# IMX7S_DEBUG.net
KiCad netlist of a schematic drawn in Altium Designer
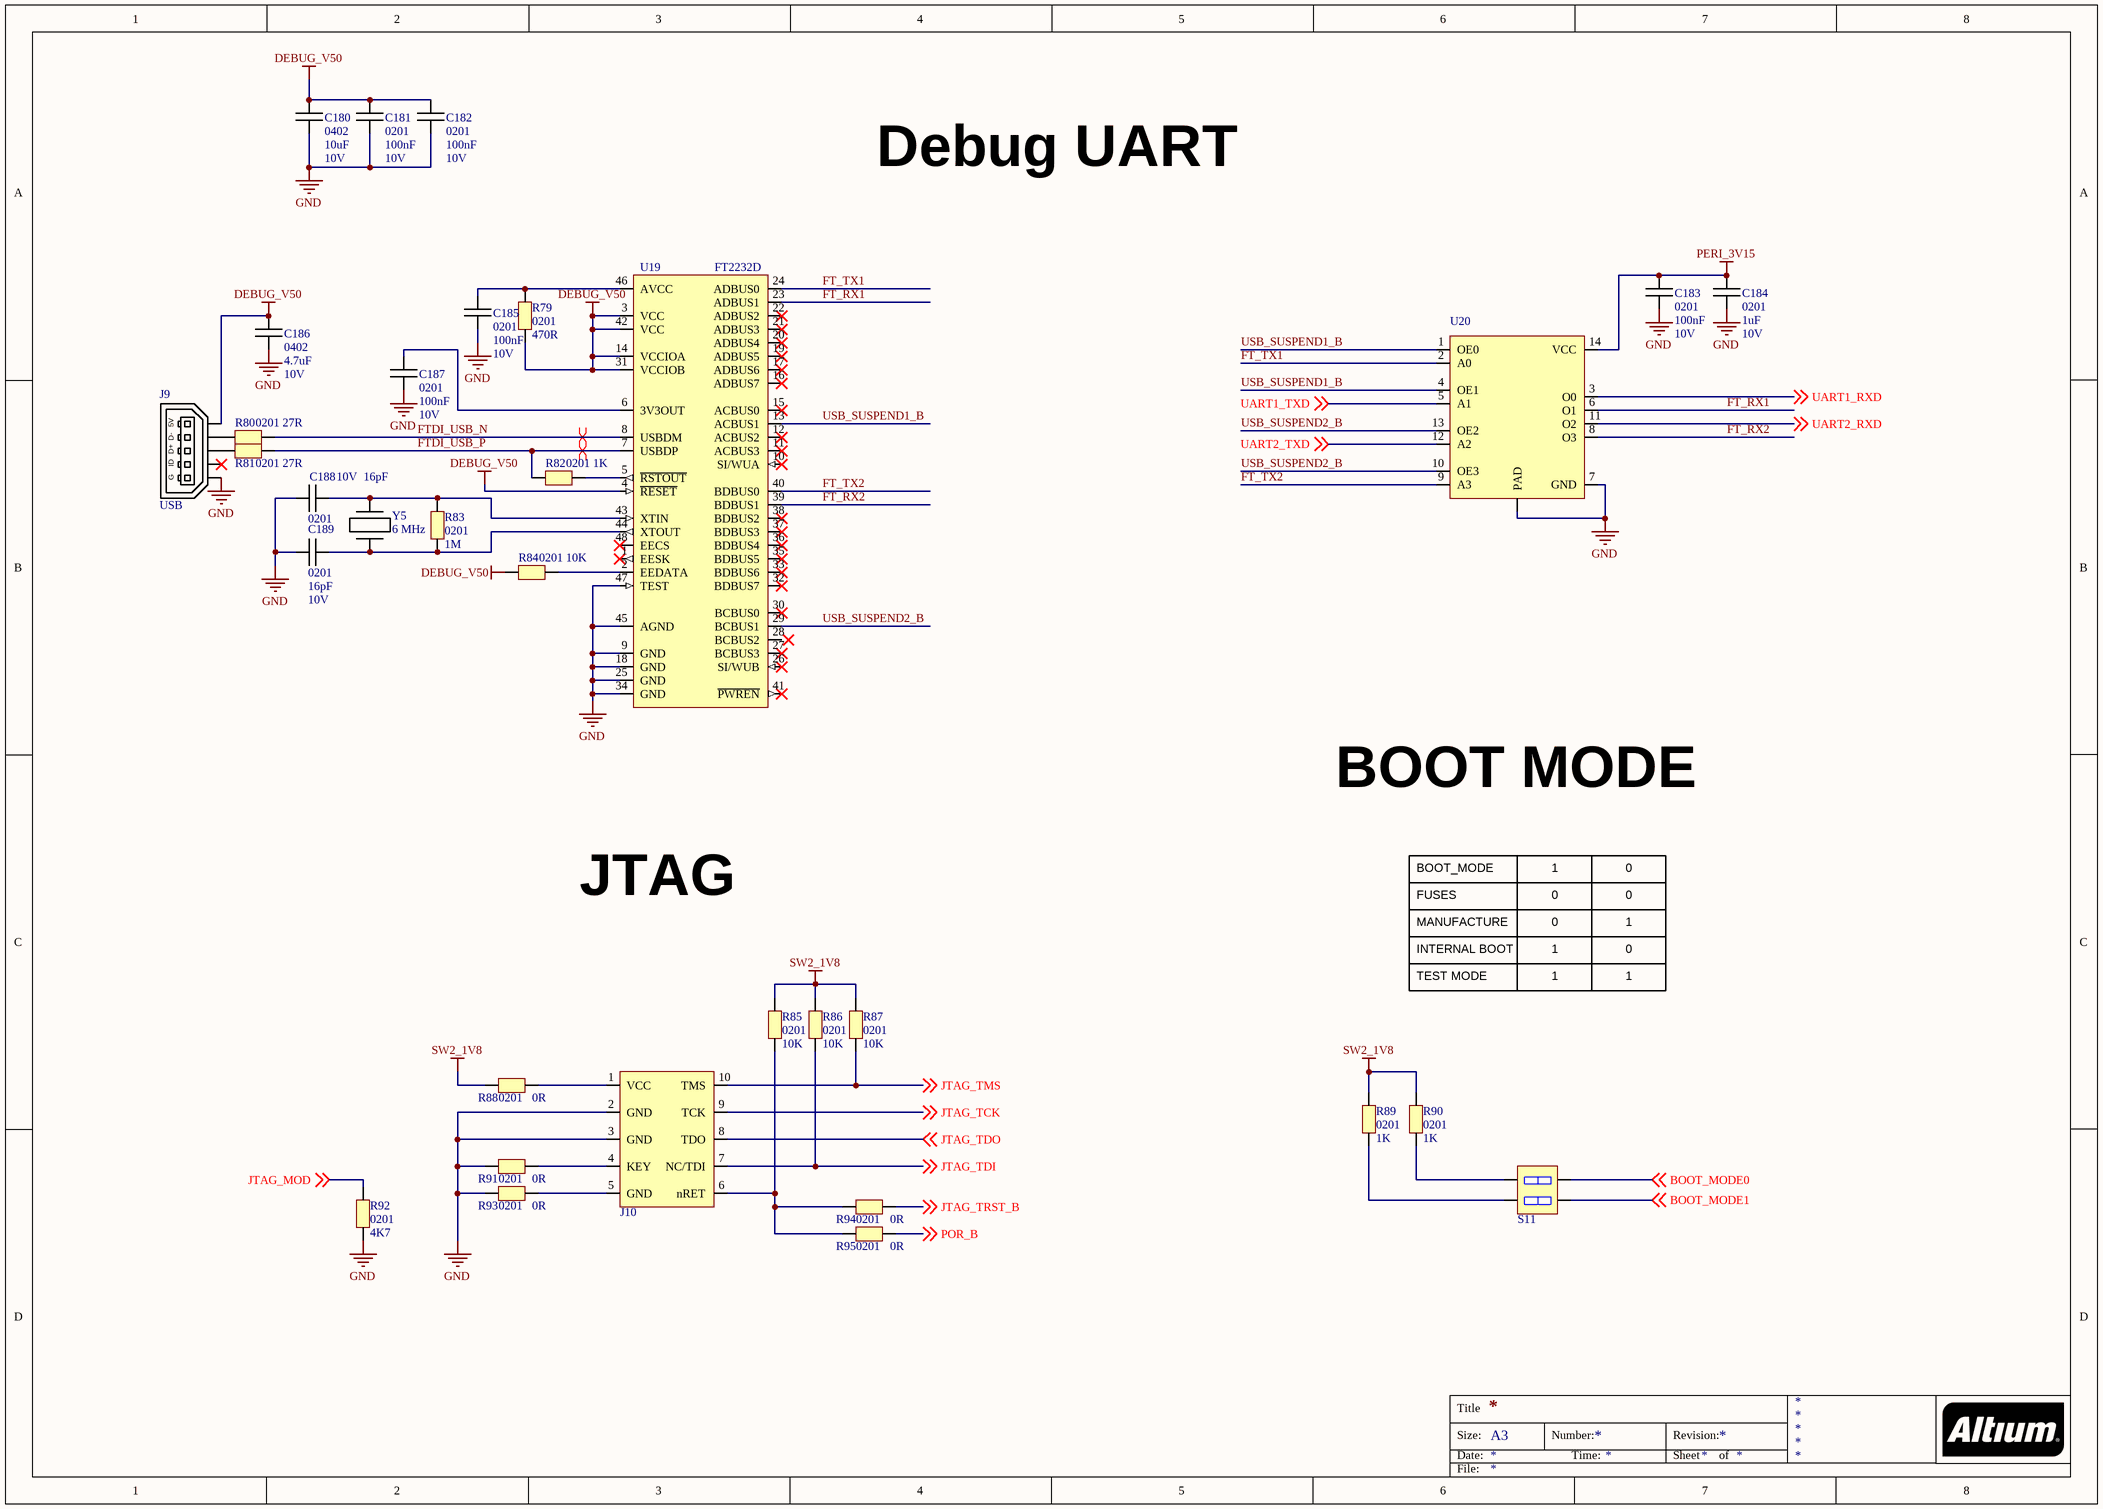
[diagram p0: IMX7S_DEBUG.SchDoc]

(export (version "E")
  (design (tool "Eeschema 10.0.6"))
  (components
    (comp (ref "C180")
      (value "10uF")
      (footprint "C0402")
      (description "Smd Multilayer Ceramic Capacitor, Grm Series, 10 F, 20%, X5r, 6.3 V, 0402 [1005 Metric]")
      (fields
        (field (name "PACKAGE") "0402")
        (field (name "VOLTAGE") "10V")
        (field (name "TOLERANCE") "20%")
        (field (name "Comment") "C0402")
      )
      (libsource (lib "Schlib_IMX7") (part "C0402"))
    )
    (comp (ref "C181")
      (value "100nF")
      (footprint "C0201")
      (description "CAP CER 0.1UF 10V X5R 0201")
      (fields
        (field (name "PACKAGE") "0201")
        (field (name "VOLTAGE") "10V")
        (field (name "TOLERANCE") "10%")
        (field (name "Comment") "C0201")
      )
      (libsource (lib "Schlib_IMX7") (part "C0201"))
    )
    (comp (ref "C182")
      (value "100nF")
      (footprint "C0201")
      (description "CAP CER 0.1UF 10V X5R 0201")
      (fields
        (field (name "PACKAGE") "0201")
        (field (name "VOLTAGE") "10V")
        (field (name "TOLERANCE") "10%")
        (field (name "Comment") "C0201")
      )
      (libsource (lib "Schlib_IMX7") (part "C0201"))
    )
    (comp (ref "C183")
      (value "100nF")
      (footprint "C0201")
      (description "CAP CER 0.1UF 10V X5R 0201")
      (fields
        (field (name "PACKAGE") "0201")
        (field (name "VOLTAGE") "10V")
        (field (name "TOLERANCE") "10%")
        (field (name "Comment") "C0201")
      )
      (libsource (lib "Schlib_IMX7") (part "C0201"))
    )
    (comp (ref "C184")
      (value "1uF")
      (footprint "C0201")
      (description "CAP CER 1UF 6.3V X5R 0201")
      (fields
        (field (name "PACKAGE") "0201")
        (field (name "VOLTAGE") "10V")
        (field (name "TOLERANCE") "20%")
        (field (name "Comment") "C0201")
      )
      (libsource (lib "Schlib_IMX7") (part "C0201"))
    )
    (comp (ref "C185")
      (value "100nF")
      (footprint "C0201")
      (description "CAP CER 0.1UF 10V X5R 0201")
      (fields
        (field (name "PACKAGE") "0201")
        (field (name "VOLTAGE") "10V")
        (field (name "TOLERANCE") "10%")
        (field (name "Comment") "C0201")
      )
      (libsource (lib "Schlib_IMX7") (part "C0201"))
    )
    (comp (ref "C186")
      (value "4.7uF")
      (footprint "C0402")
      (description "0402 10 V 4.7 uF ±20% Tolerance X5R Multilayer Ceramic Chip Capacitor")
      (fields (field (name "PACKAGE") "0402") (field (name "VOLTAGE") "10V") (field (name "Comment") "C0402"))
      (libsource (lib "Schlib_IMX7") (part "C0402"))
    )
    (comp (ref "C187")
      (value "100nF")
      (footprint "C0201")
      (description "CAP CER 0.1UF 10V X5R 0201")
      (fields
        (field (name "PACKAGE") "0201")
        (field (name "VOLTAGE") "10V")
        (field (name "TOLERANCE") "10%")
        (field (name "Comment") "C0201")
      )
      (libsource (lib "Schlib_IMX7") (part "C0201"))
    )
    (comp (ref "C188")
      (value "16pF")
      (footprint "C0201")
      (description "Multilayer Ceramic Capacitors MLCC - SMD/SMT 0201 16pF 50volts C0G +/-5%")
      (fields
        (field (name "PACKAGE") "0201")
        (field (name "VOLTAGE") "10V")
        (field (name "TOLERANCE") "5%")
        (field (name "Comment") "C0201")
      )
      (libsource (lib "Schlib_IMX7") (part "C0201"))
    )
    (comp (ref "C189")
      (value "16pF")
      (footprint "C0201")
      (description "Multilayer Ceramic Capacitors MLCC - SMD/SMT 0201 16pF 50volts C0G +/-5%")
      (fields
        (field (name "PACKAGE") "0201")
        (field (name "VOLTAGE") "10V")
        (field (name "TOLERANCE") "5%")
        (field (name "Comment") "C0201")
      )
      (libsource (lib "Schlib_IMX7") (part "C0201"))
    )
    (comp (ref "J9") (value "USB") (footprint "MICRO_USB") (libsource (lib "Schlib_IMX7") (part "MICRO_USB")))
    (comp (ref "J10")
      (value "CONN_JTAG")
      (footprint "JTAG_CONN")
      (libsource (lib "Schlib_IMX7") (part "CONN_JTAG"))
    )
    (comp (ref "R79")
      (value "470R")
      (footprint "R0201")
      (fields
        (field (name "PACKAGE") "0201")
        (field (name "VOLTAGE") "0V")
        (field (name "TOLERANCE") "1%")
        (field (name "Comment") "R0201")
      )
      (libsource (lib "") (part "R0201_1"))
    )
    (comp (ref "R80")
      (value "27R")
      (footprint "R0201")
      (description "RES SMD 27 OHM 1% 1/20W 0201")
      (fields (field (name "PACKAGE") "0201") (field (name "VOLTAGE") "0V") (field (name "TOLERANCE") "1%"))
      (libsource (lib "Schlib_IMX7") (part "R0201"))
    )
    (comp (ref "R81")
      (value "27R")
      (footprint "R0201")
      (description "RES SMD 27 OHM 1% 1/20W 0201")
      (fields (field (name "PACKAGE") "0201") (field (name "VOLTAGE") "0V") (field (name "TOLERANCE") "1%"))
      (libsource (lib "Schlib_IMX7") (part "R0201"))
    )
    (comp (ref "R82")
      (value "1K")
      (footprint "R0201")
      (fields
        (field (name "PACKAGE") "0201")
        (field (name "VOLTAGE") "0V")
        (field (name "TOLERANCE") "1%")
        (field (name "Comment") "R0201")
      )
      (libsource (lib "Schlib_IMX7") (part "R0201"))
    )
    (comp (ref "R83")
      (value "1M")
      (footprint "R0201")
      (description "RESISTOR, 0201, 1M1, 1%")
      (fields (field (name "PACKAGE") "0201") (field (name "VOLTAGE") "0V") (field (name "TOLERANCE") "1%"))
      (libsource (lib "") (part "R0201_2"))
    )
    (comp (ref "R84")
      (value "10K")
      (footprint "R0201")
      (fields
        (field (name "PACKAGE") "0201")
        (field (name "VOLTAGE") "0V")
        (field (name "TOLERANCE") "1%")
        (field (name "Comment") "R0201")
      )
      (libsource (lib "Schlib_IMX7") (part "R0201"))
    )
    (comp (ref "R85")
      (value "10K")
      (footprint "R0201")
      (fields
        (field (name "PACKAGE") "0201")
        (field (name "VOLTAGE") "0V")
        (field (name "TOLERANCE") "1%")
        (field (name "Comment") "R0201")
      )
      (libsource (lib "") (part "R0201_1"))
    )
    (comp (ref "R86")
      (value "10K")
      (footprint "R0201")
      (fields
        (field (name "PACKAGE") "0201")
        (field (name "VOLTAGE") "0V")
        (field (name "TOLERANCE") "1%")
        (field (name "Comment") "R0201")
      )
      (libsource (lib "") (part "R0201_2"))
    )
    (comp (ref "R87")
      (value "10K")
      (footprint "R0201")
      (fields
        (field (name "PACKAGE") "0201")
        (field (name "VOLTAGE") "0V")
        (field (name "TOLERANCE") "1%")
        (field (name "Comment") "R0201")
      )
      (libsource (lib "") (part "R0201_2"))
    )
    (comp (ref "R88")
      (value "0R")
      (footprint "R0201")
      (description "MULTICOMP - MCRE000086 - RES, 0R0, 1%, 0.05W, 0201, THICK FILM")
      (fields (field (name "PACKAGE") "0201") (field (name "VOLTAGE") "0V") (field (name "TOLERANCE") "1%"))
      (libsource (lib "Schlib_IMX7") (part "R0201"))
    )
    (comp (ref "R89")
      (value "1K")
      (footprint "R0201")
      (fields
        (field (name "PACKAGE") "0201")
        (field (name "VOLTAGE") "0V")
        (field (name "TOLERANCE") "1%")
        (field (name "Comment") "R0201")
      )
      (libsource (lib "") (part "R0201_1"))
    )
    (comp (ref "R90")
      (value "1K")
      (footprint "R0201")
      (fields
        (field (name "PACKAGE") "0201")
        (field (name "VOLTAGE") "0V")
        (field (name "TOLERANCE") "1%")
        (field (name "Comment") "R0201")
      )
      (libsource (lib "") (part "R0201_1"))
    )
    (comp (ref "R91")
      (value "0R")
      (footprint "R0201")
      (description "MULTICOMP - MCRE000086 - RES, 0R0, 1%, 0.05W, 0201, THICK FILM")
      (fields (field (name "PACKAGE") "0201") (field (name "VOLTAGE") "0V") (field (name "TOLERANCE") "1%"))
      (libsource (lib "Schlib_IMX7") (part "R0201"))
    )
    (comp (ref "R92")
      (value "4K7")
      (footprint "R0201")
      (description "RES SMD 4.7K OHM 1% 1/20W 0201")
      (fields (field (name "PACKAGE") "0201") (field (name "VOLTAGE") "0V") (field (name "TOLERANCE") "1%"))
      (libsource (lib "") (part "R0201_2"))
    )
    (comp (ref "R93")
      (value "0R")
      (footprint "R0201")
      (description "MULTICOMP - MCRE000086 - RES, 0R0, 1%, 0.05W, 0201, THICK FILM")
      (fields (field (name "PACKAGE") "0201") (field (name "VOLTAGE") "0V") (field (name "TOLERANCE") "1%"))
      (libsource (lib "Schlib_IMX7") (part "R0201"))
    )
    (comp (ref "R94")
      (value "0R")
      (footprint "R0201")
      (description "MULTICOMP - MCRE000086 - RES, 0R0, 1%, 0.05W, 0201, THICK FILM")
      (fields (field (name "PACKAGE") "0201") (field (name "VOLTAGE") "0V") (field (name "TOLERANCE") "1%"))
      (libsource (lib "Schlib_IMX7") (part "R0201"))
    )
    (comp (ref "R95")
      (value "0R")
      (footprint "R0201")
      (description "MULTICOMP - MCRE000086 - RES, 0R0, 1%, 0.05W, 0201, THICK FILM")
      (fields (field (name "PACKAGE") "0201") (field (name "VOLTAGE") "0V") (field (name "TOLERANCE") "1%"))
      (libsource (lib "Schlib_IMX7") (part "R0201"))
    )
    (comp (ref "S11")
      (value "mikroswitch")
      (footprint "DIP_SWITCH")
      (libsource (lib "Schlib_IMX7") (part "mikroswitch"))
    )
    (comp (ref "U19")
      (value "FT2232D")
      (footprint "LQFP48")
      (description "USB Full Speed to Dual Channel Serial UART/FIFO/JTAG/SPI/I2C IC - LQFP-48")
      (fields (field (name "MF") "FTDI,") (field (name "MP") "FT2232D-REEL"))
      (libsource (lib "Schlib_IMX7") (part "FT2232D"))
    )
    (comp (ref "U20")
      (value "74LCX126BQX")
      (footprint "DQFN14")
      (description "IC BUFFER QUAD LV N-INV 14DQFN")
      (libsource (lib "Schlib_IMX7") (part "74LCX126BQX"))
    )
    (comp (ref "Y5") (value "6 MHz") (footprint "HC49") (libsource (lib "Schlib_IMX7") (part "QUARTZ_6MHz")))
  )
  (nets
    (net (code "1") (name "/FTDI_USB_N") (class "Default")
      (node (ref "R80") (pin "1") (pinfunction "1_1") (pintype "passive"))
      (node (ref "U19") (pin "8") (pinfunction "USBDM_8") (pintype "bidirectional"))
    )
    (net (code "2") (name "/FTDI_USB_P") (class "Default")
      (node (ref "R81") (pin "1") (pinfunction "1_1") (pintype "passive"))
      (node (ref "R82") (pin "2") (pinfunction "2_2") (pintype "passive"))
      (node (ref "U19") (pin "7") (pinfunction "USBDP_7") (pintype "bidirectional"))
    )
    (net (code "3") (name "/FT_RX1") (class "Default")
      (node (ref "U19") (pin "23") (pinfunction "ADBUS1_23") (pintype "bidirectional"))
      (node (ref "U20") (pin "6") (pinfunction "O1_6") (pintype "passive"))
    )
    (net (code "4") (name "/FT_RX2") (class "Default")
      (node (ref "U19") (pin "39") (pinfunction "BDBUS1_39") (pintype "bidirectional"))
      (node (ref "U20") (pin "8") (pinfunction "O3_8") (pintype "passive"))
    )
    (net (code "5") (name "/FT_TX1") (class "Default")
      (node (ref "U19") (pin "24") (pinfunction "ADBUS0_24") (pintype "bidirectional"))
      (node (ref "U20") (pin "2") (pinfunction "A0_2") (pintype "passive"))
    )
    (net (code "6") (name "/FT_TX2") (class "Default")
      (node (ref "U19") (pin "40") (pinfunction "BDBUS0_40") (pintype "bidirectional"))
      (node (ref "U20") (pin "9") (pinfunction "A3_9") (pintype "passive"))
    )
    (net (code "7") (name "/USB_SUSPEND1_B") (class "Default")
      (node (ref "U19") (pin "13") (pinfunction "ACBUS1_13") (pintype "bidirectional"))
      (node (ref "U20") (pin "1") (pinfunction "OE0_1") (pintype "passive"))
      (node (ref "U20") (pin "4") (pinfunction "OE1_4") (pintype "passive"))
    )
    (net (code "8") (name "/USB_SUSPEND2_B") (class "Default")
      (node (ref "U19") (pin "29") (pinfunction "BCBUS1_29") (pintype "bidirectional"))
      (node (ref "U20") (pin "10") (pinfunction "OE3_10") (pintype "passive"))
      (node (ref "U20") (pin "13") (pinfunction "OE2_13") (pintype "passive"))
    )
    (net (code "9") (name "BOOT_MODE0") (class "Default")
      (node (ref "S11") (pin "4") (pinfunction "4_4") (pintype "passive"))
    )
    (net (code "10") (name "BOOT_MODE1") (class "Default")
      (node (ref "S11") (pin "3") (pinfunction "3_3") (pintype "passive"))
    )
    (net (code "11") (name "DEBUG_V50") (class "Default")
      (node (ref "C180") (pin "2") (pinfunction "2_2") (pintype "passive"))
      (node (ref "C181") (pin "2") (pinfunction "2_2") (pintype "passive"))
      (node (ref "C182") (pin "2") (pinfunction "2_2") (pintype "passive"))
      (node (ref "C186") (pin "2") (pinfunction "2_2") (pintype "passive"))
      (node (ref "J9") (pin "1") (pinfunction "5V_1") (pintype "passive"))
      (node (ref "R79") (pin "1") (pinfunction "1_1") (pintype "passive"))
      (node (ref "R84") (pin "2") (pinfunction "2_2") (pintype "passive"))
      (node (ref "U19") (pin "14") (pinfunction "VCCIOA_14") (pintype "power_in"))
      (node (ref "U19") (pin "3") (pinfunction "VCC_3") (pintype "power_in"))
      (node (ref "U19") (pin "31") (pinfunction "VCCIOB_31") (pintype "power_in"))
      (node (ref "U19") (pin "4") (pinfunction "~{RESET}_4") (pintype "input"))
      (node (ref "U19") (pin "42") (pinfunction "VCC_42") (pintype "power_in"))
    )
    (net (code "12") (name "GND") (class "Default")
      (node (ref "C180") (pin "1") (pinfunction "1_1") (pintype "passive"))
      (node (ref "C181") (pin "1") (pinfunction "1_1") (pintype "passive"))
      (node (ref "C182") (pin "1") (pinfunction "1_1") (pintype "passive"))
      (node (ref "C183") (pin "1") (pinfunction "1_1") (pintype "passive"))
      (node (ref "C184") (pin "1") (pinfunction "1_1") (pintype "passive"))
      (node (ref "C185") (pin "1") (pinfunction "1_1") (pintype "passive"))
      (node (ref "C186") (pin "1") (pinfunction "1_1") (pintype "passive"))
      (node (ref "C187") (pin "1") (pinfunction "1_1") (pintype "passive"))
      (node (ref "C188") (pin "2") (pinfunction "2_2") (pintype "passive"))
      (node (ref "C189") (pin "2") (pinfunction "2_2") (pintype "passive"))
      (node (ref "J10") (pin "2") (pinfunction "GND_2") (pintype "passive"))
      (node (ref "J10") (pin "3") (pinfunction "GND_3") (pintype "passive"))
      (node (ref "J9") (pin "5") (pinfunction "GND_5") (pintype "passive"))
      (node (ref "R91") (pin "2") (pinfunction "2_2") (pintype "passive"))
      (node (ref "R92") (pin "2") (pinfunction "2_2") (pintype "passive"))
      (node (ref "R93") (pin "2") (pinfunction "2_2") (pintype "passive"))
      (node (ref "U19") (pin "18") (pinfunction "GND_18") (pintype "power_in"))
      (node (ref "U19") (pin "25") (pinfunction "GND_25") (pintype "power_in"))
      (node (ref "U19") (pin "34") (pinfunction "GND_34") (pintype "power_in"))
      (node (ref "U19") (pin "45") (pinfunction "AGND_45") (pintype "power_in"))
      (node (ref "U19") (pin "47") (pinfunction "TEST_47") (pintype "input"))
      (node (ref "U19") (pin "9") (pinfunction "GND_9") (pintype "power_in"))
      (node (ref "U20") (pin "0") (pinfunction "PAD_0") (pintype "passive"))
      (node (ref "U20") (pin "7") (pinfunction "GND_7") (pintype "passive"))
    )
    (net (code "13") (name "JTAG_MOD") (class "Default")
      (node (ref "R92") (pin "1") (pinfunction "1_1") (pintype "passive"))
    )
    (net (code "14") (name "JTAG_TCK") (class "Default")
      (node (ref "J10") (pin "9") (pinfunction "TCK_9") (pintype "passive"))
    )
    (net (code "15") (name "JTAG_TDI") (class "Default")
      (node (ref "J10") (pin "7") (pinfunction "NC/TDI_7") (pintype "passive"))
      (node (ref "R86") (pin "2") (pinfunction "2_2") (pintype "passive"))
    )
    (net (code "16") (name "JTAG_TDO") (class "Default")
      (node (ref "J10") (pin "8") (pinfunction "TDO_8") (pintype "passive"))
    )
    (net (code "17") (name "JTAG_TMS") (class "Default")
      (node (ref "J10") (pin "10") (pinfunction "TMS_10") (pintype "passive"))
      (node (ref "R87") (pin "2") (pinfunction "2_2") (pintype "passive"))
    )
    (net (code "18") (name "JTAG_TRST_B") (class "Default")
      (node (ref "R94") (pin "1") (pinfunction "1_1") (pintype "passive"))
    )
    (net (code "19") (name "Net-(J9-D+)") (class "Default")
      (node (ref "J9") (pin "3") (pinfunction "D+_3") (pintype "passive"))
      (node (ref "R81") (pin "2") (pinfunction "2_2") (pintype "passive"))
    )
    (net (code "20") (name "Net-(J9-D-)") (class "Default")
      (node (ref "J9") (pin "2") (pinfunction "D-_2") (pintype "passive"))
      (node (ref "R80") (pin "2") (pinfunction "2_2") (pintype "passive"))
    )
    (net (code "21") (name "Net-(J10-GND-Pad5)") (class "Default")
      (node (ref "J10") (pin "5") (pinfunction "GND_5") (pintype "passive"))
      (node (ref "R93") (pin "1") (pinfunction "1_1") (pintype "passive"))
    )
    (net (code "22") (name "Net-(J10-KEY)") (class "Default")
      (node (ref "J10") (pin "4") (pinfunction "KEY_4") (pintype "passive"))
      (node (ref "R91") (pin "1") (pinfunction "1_1") (pintype "passive"))
    )
    (net (code "23") (name "Net-(J10-VCC)") (class "Default")
      (node (ref "J10") (pin "1") (pinfunction "VCC_1") (pintype "passive"))
      (node (ref "R88") (pin "1") (pinfunction "1_1") (pintype "passive"))
    )
    (net (code "24") (name "Net-(J10-nRET)") (class "Default")
      (node (ref "J10") (pin "6") (pinfunction "nRET_6") (pintype "passive"))
      (node (ref "R85") (pin "1") (pinfunction "1_1") (pintype "passive"))
      (node (ref "R94") (pin "2") (pinfunction "2_2") (pintype "passive"))
      (node (ref "R95") (pin "2") (pinfunction "2_2") (pintype "passive"))
    )
    (net (code "25") (name "Net-(R89-Pad1)") (class "Default")
      (node (ref "R89") (pin "1") (pinfunction "1_1") (pintype "passive"))
      (node (ref "S11") (pin "2") (pinfunction "2_2") (pintype "passive"))
    )
    (net (code "26") (name "Net-(R90-Pad1)") (class "Default")
      (node (ref "R90") (pin "1") (pinfunction "1_1") (pintype "passive"))
      (node (ref "S11") (pin "1") (pinfunction "1_1") (pintype "passive"))
    )
    (net (code "27") (name "Net-(U19-3V3OUT)") (class "Default")
      (node (ref "C187") (pin "2") (pinfunction "2_2") (pintype "passive"))
      (node (ref "U19") (pin "6") (pinfunction "3V3OUT_6") (pintype "power_in"))
    )
    (net (code "28") (name "Net-(U19-AVCC)") (class "Default")
      (node (ref "C185") (pin "2") (pinfunction "2_2") (pintype "passive"))
      (node (ref "R79") (pin "2") (pinfunction "2_2") (pintype "passive"))
      (node (ref "U19") (pin "46") (pinfunction "AVCC_46") (pintype "power_in"))
    )
    (net (code "29") (name "Net-(U19-EEDATA)") (class "Default")
      (node (ref "R84") (pin "1") (pinfunction "1_1") (pintype "passive"))
      (node (ref "U19") (pin "2") (pinfunction "EEDATA_2") (pintype "bidirectional"))
    )
    (net (code "30") (name "Net-(U19-XTIN)") (class "Default")
      (node (ref "C188") (pin "1") (pinfunction "1_1") (pintype "passive"))
      (node (ref "R83") (pin "1") (pinfunction "1_1") (pintype "passive"))
      (node (ref "U19") (pin "43") (pinfunction "XTIN_43") (pintype "input"))
      (node (ref "Y5") (pin "2") (pintype "passive"))
    )
    (net (code "31") (name "Net-(U19-XTOUT)") (class "Default")
      (node (ref "C189") (pin "1") (pinfunction "1_1") (pintype "passive"))
      (node (ref "R83") (pin "2") (pinfunction "2_2") (pintype "passive"))
      (node (ref "U19") (pin "44") (pinfunction "XTOUT_44") (pintype "output"))
      (node (ref "Y5") (pin "1") (pintype "passive"))
    )
    (net (code "32") (name "Net-(U19-~{RSTOUT})") (class "Default")
      (node (ref "R82") (pin "1") (pinfunction "1_1") (pintype "passive"))
      (node (ref "U19") (pin "5") (pinfunction "~{RSTOUT}_5") (pintype "output"))
    )
    (net (code "33") (name "PERI_3V15") (class "Default")
      (node (ref "C183") (pin "2") (pinfunction "2_2") (pintype "passive"))
      (node (ref "C184") (pin "2") (pinfunction "2_2") (pintype "passive"))
      (node (ref "U20") (pin "14") (pinfunction "VCC_14") (pintype "passive"))
    )
    (net (code "34") (name "POR_B") (class "Default")
      (node (ref "R95") (pin "1") (pinfunction "1_1") (pintype "passive"))
    )
    (net (code "35") (name "SW2_1V8") (class "Default")
      (node (ref "R85") (pin "2") (pinfunction "2_2") (pintype "passive"))
      (node (ref "R86") (pin "1") (pinfunction "1_1") (pintype "passive"))
      (node (ref "R87") (pin "1") (pinfunction "1_1") (pintype "passive"))
      (node (ref "R88") (pin "2") (pinfunction "2_2") (pintype "passive"))
      (node (ref "R89") (pin "2") (pinfunction "2_2") (pintype "passive"))
      (node (ref "R90") (pin "2") (pinfunction "2_2") (pintype "passive"))
    )
    (net (code "36") (name "UART1_RXD") (class "Default")
      (node (ref "U20") (pin "3") (pinfunction "O0_3") (pintype "passive"))
    )
    (net (code "37") (name "UART1_TXD") (class "Default")
      (node (ref "U20") (pin "5") (pinfunction "A1_5") (pintype "passive"))
    )
    (net (code "38") (name "UART2_RXD") (class "Default")
      (node (ref "U20") (pin "11") (pinfunction "O2_11") (pintype "passive"))
    )
    (net (code "39") (name "UART2_TXD") (class "Default")
      (node (ref "U20") (pin "12") (pinfunction "A2_12") (pintype "passive"))
    )
    (net (code "40") (name "unconnected-(J9-ID-Pad4)") (class "Default")
      (node (ref "J9") (pin "4") (pinfunction "ID_4") (pintype "passive+no_connect"))
    )
    (net (code "41") (name "unconnected-(U19-ACBUS0-Pad15)") (class "Default")
      (node (ref "U19") (pin "15") (pinfunction "ACBUS0_15") (pintype "bidirectional+no_connect"))
    )
    (net (code "42") (name "unconnected-(U19-ACBUS2-Pad12)") (class "Default")
      (node (ref "U19") (pin "12") (pinfunction "ACBUS2_12") (pintype "bidirectional+no_connect"))
    )
    (net (code "43") (name "unconnected-(U19-ACBUS3-Pad11)") (class "Default")
      (node (ref "U19") (pin "11") (pinfunction "ACBUS3_11") (pintype "bidirectional+no_connect"))
    )
    (net (code "44") (name "unconnected-(U19-ADBUS2-Pad22)") (class "Default")
      (node (ref "U19") (pin "22") (pinfunction "ADBUS2_22") (pintype "bidirectional+no_connect"))
    )
    (net (code "45") (name "unconnected-(U19-ADBUS3-Pad21)") (class "Default")
      (node (ref "U19") (pin "21") (pinfunction "ADBUS3_21") (pintype "bidirectional+no_connect"))
    )
    (net (code "46") (name "unconnected-(U19-ADBUS4-Pad20)") (class "Default")
      (node (ref "U19") (pin "20") (pinfunction "ADBUS4_20") (pintype "bidirectional+no_connect"))
    )
    (net (code "47") (name "unconnected-(U19-ADBUS5-Pad19)") (class "Default")
      (node (ref "U19") (pin "19") (pinfunction "ADBUS5_19") (pintype "bidirectional+no_connect"))
    )
    (net (code "48") (name "unconnected-(U19-ADBUS6-Pad17)") (class "Default")
      (node (ref "U19") (pin "17") (pinfunction "ADBUS6_17") (pintype "bidirectional+no_connect"))
    )
    (net (code "49") (name "unconnected-(U19-ADBUS7-Pad16)") (class "Default")
      (node (ref "U19") (pin "16") (pinfunction "ADBUS7_16") (pintype "bidirectional+no_connect"))
    )
    (net (code "50") (name "unconnected-(U19-BCBUS0-Pad30)") (class "Default")
      (node (ref "U19") (pin "30") (pinfunction "BCBUS0_30") (pintype "bidirectional+no_connect"))
    )
    (net (code "51") (name "unconnected-(U19-BCBUS2-Pad28)") (class "Default")
      (node (ref "U19") (pin "28") (pinfunction "BCBUS2_28") (pintype "bidirectional"))
    )
    (net (code "52") (name "unconnected-(U19-BCBUS3-Pad27)") (class "Default")
      (node (ref "U19") (pin "27") (pinfunction "BCBUS3_27") (pintype "bidirectional+no_connect"))
    )
    (net (code "53") (name "unconnected-(U19-BDBUS2-Pad38)") (class "Default")
      (node (ref "U19") (pin "38") (pinfunction "BDBUS2_38") (pintype "bidirectional+no_connect"))
    )
    (net (code "54") (name "unconnected-(U19-BDBUS3-Pad37)") (class "Default")
      (node (ref "U19") (pin "37") (pinfunction "BDBUS3_37") (pintype "bidirectional+no_connect"))
    )
    (net (code "55") (name "unconnected-(U19-BDBUS4-Pad36)") (class "Default")
      (node (ref "U19") (pin "36") (pinfunction "BDBUS4_36") (pintype "bidirectional+no_connect"))
    )
    (net (code "56") (name "unconnected-(U19-BDBUS5-Pad35)") (class "Default")
      (node (ref "U19") (pin "35") (pinfunction "BDBUS5_35") (pintype "bidirectional+no_connect"))
    )
    (net (code "57") (name "unconnected-(U19-BDBUS6-Pad33)") (class "Default")
      (node (ref "U19") (pin "33") (pinfunction "BDBUS6_33") (pintype "bidirectional+no_connect"))
    )
    (net (code "58") (name "unconnected-(U19-BDBUS7-Pad32)") (class "Default")
      (node (ref "U19") (pin "32") (pinfunction "BDBUS7_32") (pintype "bidirectional+no_connect"))
    )
    (net (code "59") (name "unconnected-(U19-EECS-Pad48)") (class "Default")
      (node (ref "U19") (pin "48") (pinfunction "EECS_48") (pintype "bidirectional+no_connect"))
    )
    (net (code "60") (name "unconnected-(U19-EESK-Pad1)") (class "Default")
      (node (ref "U19") (pin "1") (pinfunction "EESK_1") (pintype "output+no_connect"))
    )
    (net (code "61") (name "unconnected-(U19-SI{slash}WUA-Pad10)") (class "Default")
      (node (ref "U19") (pin "10") (pinfunction "SI/WUA_10") (pintype "input+no_connect"))
    )
    (net (code "62") (name "unconnected-(U19-SI{slash}WUB-Pad26)") (class "Default")
      (node (ref "U19") (pin "26") (pinfunction "SI/WUB_26") (pintype "input+no_connect"))
    )
    (net (code "63") (name "unconnected-(U19-~{PWREN}-Pad41)") (class "Default")
      (node (ref "U19") (pin "41") (pinfunction "~{PWREN}_41") (pintype "output+no_connect"))
    )
  )
)
